# Power.net
KiCad netlist of a schematic drawn in Altium Designer
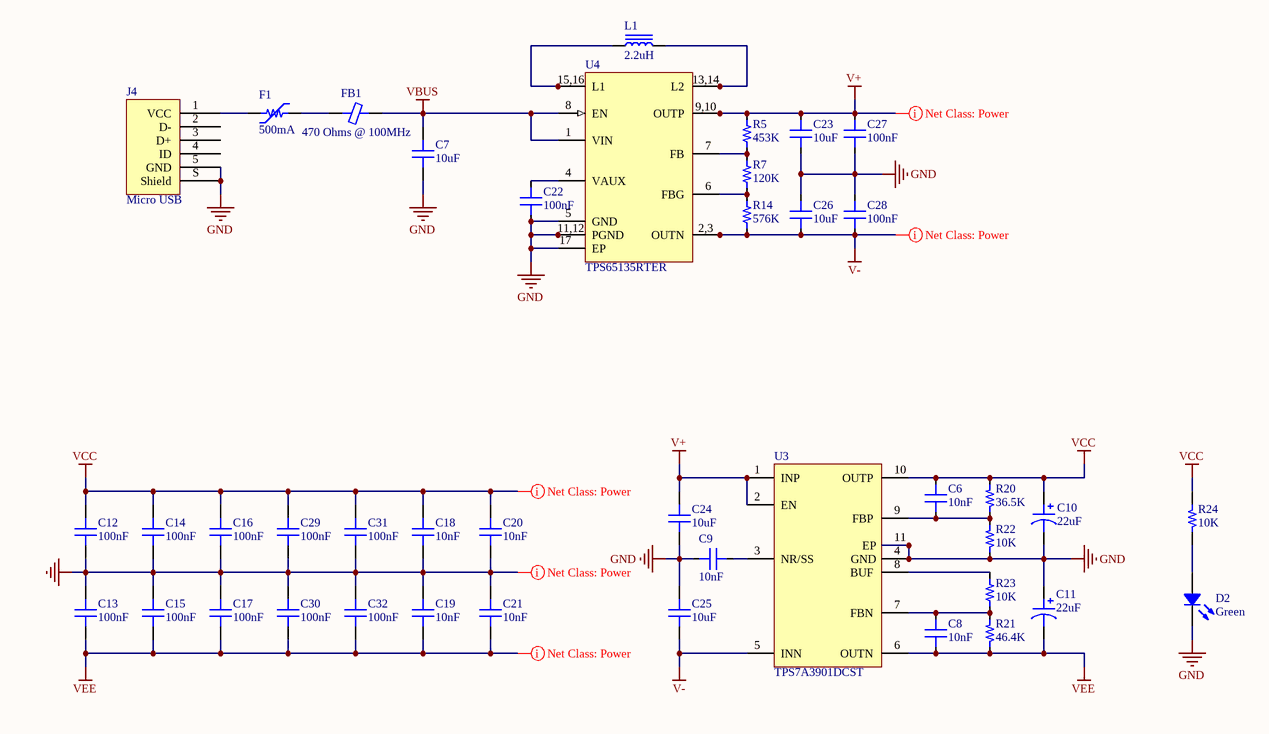
[diagram p0: Power.SchDoc]

(export (version "E")
  (design (tool "Eeschema 10.0.6"))
  (components
    (comp (ref "C6")
      (value "10nF")
      (footprint "CAP 0402/1005")
      (description "CAP CER 10NF 25V NP0 0402")
      (fields (field (name "MANUFACTURER") "Murata") (field (name "TOLERANCE") "2%"))
      (libsource (lib "") (part "Capacitor_1"))
    )
    (comp (ref "C7")
      (value "10uF")
      (footprint "CAP 0603/1608")
      (description "CAP CER 10UF 16V X5R 0603")
      (fields
        (field (name "PART NUMBER") "GRM188R61C106MA73D")
        (field (name "MANUFACTURER") "Murata Electronics North America")
      )
      (libsource (lib "Mengsklib") (part "Capacitor"))
    )
    (comp (ref "C8")
      (value "10nF")
      (footprint "CAP 0402/1005")
      (description "CAP CER 10NF 25V NP0 0402")
      (fields (field (name "MANUFACTURER") "Murata") (field (name "TOLERANCE") "2%"))
      (libsource (lib "") (part "Capacitor_1"))
    )
    (comp (ref "C9")
      (value "10nF")
      (footprint "CAP 0402/1005")
      (description "CAP CER 10NF 25V NP0 0402")
      (fields (field (name "MANUFACTURER") "Murata") (field (name "TOLERANCE") "2%"))
      (libsource (lib "") (part "Capacitor_1"))
    )
    (comp (ref "C10")
      (value "22uF")
      (footprint "CAP TAN 3528 - 2.1MM")
      (description "CAP TANT 22UF 16V 3528")
      (fields (field (name "MANUFACTURER") "AVX") (field (name "TOLERANCE") "20%"))
      (libsource (lib "Mengsklib") (part "Polarised Capacitor"))
    )
    (comp (ref "C11")
      (value "22uF")
      (footprint "CAP TAN 3528 - 2.1MM")
      (description "CAP TANT 22UF 16V 3528")
      (fields (field (name "MANUFACTURER") "AVX") (field (name "TOLERANCE") "20%"))
      (libsource (lib "Mengsklib") (part "Polarised Capacitor"))
    )
    (comp (ref "C12")
      (value "100nF")
      (footprint "CAP 0402/1005")
      (description "CAP CER 100NF 25V X5R 0402")
      (fields (field (name "MANUFACTURER") "Murata") (field (name "TOLERANCE") "10%"))
      (libsource (lib "Mengsklib") (part "Capacitor"))
    )
    (comp (ref "C13")
      (value "100nF")
      (footprint "CAP 0402/1005")
      (description "CAP CER 100NF 25V X5R 0402")
      (fields (field (name "MANUFACTURER") "Murata") (field (name "TOLERANCE") "10%"))
      (libsource (lib "Mengsklib") (part "Capacitor"))
    )
    (comp (ref "C14")
      (value "100nF")
      (footprint "CAP 0204/0510")
      (description "CAP CER 100NF 25V X5R 0204")
      (fields (field (name "PART NUMBER") "MSRLT103SB5104MFNA01") (field (name "MANUFACTURER") "Taiyo Yuden"))
      (libsource (lib "Mengsklib") (part "Capacitor"))
    )
    (comp (ref "C15")
      (value "100nF")
      (footprint "CAP 0204/0510")
      (description "CAP CER 100NF 25V X5R 0204")
      (fields (field (name "PART NUMBER") "MSRLT103SB5104MFNA01") (field (name "MANUFACTURER") "Taiyo Yuden"))
      (libsource (lib "Mengsklib") (part "Capacitor"))
    )
    (comp (ref "C16")
      (value "100nF")
      (footprint "CAP 0204/0510")
      (description "CAP CER 100NF 25V X5R 0204")
      (fields (field (name "PART NUMBER") "MSRLT103SB5104MFNA01") (field (name "MANUFACTURER") "Taiyo Yuden"))
      (libsource (lib "Mengsklib") (part "Capacitor"))
    )
    (comp (ref "C17")
      (value "100nF")
      (footprint "CAP 0204/0510")
      (description "CAP CER 100NF 25V X5R 0204")
      (fields (field (name "PART NUMBER") "MSRLT103SB5104MFNA01") (field (name "MANUFACTURER") "Taiyo Yuden"))
      (libsource (lib "Mengsklib") (part "Capacitor"))
    )
    (comp (ref "C18")
      (value "10nF")
      (footprint "CAP 0402/1005")
      (description "CAP CER 10NF 25V NP0 0402")
      (fields (field (name "PART NUMBER") "GRM1555C1E103GE01D") (field (name "TOLERANCE") "2%"))
      (libsource (lib "Mengsklib") (part "Capacitor"))
    )
    (comp (ref "C19")
      (value "10nF")
      (footprint "CAP 0402/1005")
      (description "CAP CER 10NF 25V NP0 0402")
      (fields (field (name "PART NUMBER") "GRM1555C1E103GE01D") (field (name "TOLERANCE") "2%"))
      (libsource (lib "Mengsklib") (part "Capacitor"))
    )
    (comp (ref "C20")
      (value "10nF")
      (footprint "CAP 0402/1005")
      (description "CAP CER 10NF 25V NP0 0402")
      (fields (field (name "PART NUMBER") "GRM1555C1E103GE01D") (field (name "TOLERANCE") "2%"))
      (libsource (lib "Mengsklib") (part "Capacitor"))
    )
    (comp (ref "C21")
      (value "10nF")
      (footprint "CAP 0402/1005")
      (description "CAP CER 10NF 25V NP0 0402")
      (fields (field (name "PART NUMBER") "GRM1555C1E103GE01D") (field (name "TOLERANCE") "2%"))
      (libsource (lib "Mengsklib") (part "Capacitor"))
    )
    (comp (ref "C22")
      (value "100nF")
      (footprint "CAP 0402/1005")
      (description "CAP CER 100NF 25V X5R 0402")
      (fields (field (name "PART NUMBER") "GRM155R61E104KA87D") (field (name "MANUFACTURER") "Murata"))
      (libsource (lib "") (part "Capacitor_1"))
    )
    (comp (ref "C23")
      (value "10uF")
      (footprint "CAP 0603/1608")
      (description "CAP CER 10UF 16V X5R 0603")
      (fields
        (field (name "PART NUMBER") "GRM188R61C106MA73D")
        (field (name "MANUFACTURER") "Murata Electronics North America")
      )
      (libsource (lib "") (part "Capacitor_1"))
    )
    (comp (ref "C24")
      (value "10uF")
      (footprint "CAP 0603/1608")
      (description "CAP CER 10UF 16V X5R 0603")
      (fields (field (name "MANUFACTURER") "Murata") (field (name "PART NUMBER") "GRM188R61C106MA73D"))
      (libsource (lib "Mengsklib") (part "Capacitor"))
    )
    (comp (ref "C25")
      (value "10uF")
      (footprint "CAP 0603/1608")
      (description "CAP CER 10UF 16V X5R 0603")
      (fields (field (name "MANUFACTURER") "Murata") (field (name "PART NUMBER") "GRM188R61C106MA73D"))
      (libsource (lib "Mengsklib") (part "Capacitor"))
    )
    (comp (ref "C26")
      (value "10uF")
      (footprint "CAP 0603/1608")
      (description "CAP CER 10UF 16V X5R 0603")
      (fields
        (field (name "PART NUMBER") "GRM188R61C106MA73D")
        (field (name "MANUFACTURER") "Murata Electronics North America")
      )
      (libsource (lib "") (part "Capacitor_1"))
    )
    (comp (ref "C27")
      (value "100nF")
      (footprint "CAP 0402/1005")
      (description "CAP CER 100NF 25V X5R 0402")
      (fields
        (field (name "PART NUMBER") "GRM155R61E104KA87D")
        (field (name "MANUFACTURER") "Murata Electronics North America")
      )
      (libsource (lib "") (part "Capacitor_1"))
    )
    (comp (ref "C28")
      (value "100nF")
      (footprint "CAP 0402/1005")
      (description "CAP CER 100NF 25V X5R 0402")
      (fields
        (field (name "PART NUMBER") "GRM155R61E104KA87D")
        (field (name "MANUFACTURER") "Murata Electronics North America")
      )
      (libsource (lib "") (part "Capacitor_1"))
    )
    (comp (ref "C29")
      (value "100nF")
      (footprint "CAP 0204/0510")
      (description "CAP CER 100NF 25V X5R 0204")
      (fields (field (name "MANUFACTURER") "Taiyo Yuden") (field (name "TOLERANCE") "20%"))
      (libsource (lib "Mengsklib") (part "Capacitor"))
    )
    (comp (ref "C30")
      (value "100nF")
      (footprint "CAP 0204/0510")
      (description "CAP CER 100NF 25V X5R 0204")
      (fields (field (name "MANUFACTURER") "Taiyo Yuden") (field (name "TOLERANCE") "20%"))
      (libsource (lib "Mengsklib") (part "Capacitor"))
    )
    (comp (ref "C31")
      (value "100nF")
      (footprint "CAP 0204/0510")
      (description "CAP CER 100NF 25V X5R 0204")
      (fields (field (name "MANUFACTURER") "Taiyo Yuden") (field (name "TOLERANCE") "20%"))
      (libsource (lib "Mengsklib") (part "Capacitor"))
    )
    (comp (ref "C32")
      (value "100nF")
      (footprint "CAP 0204/0510")
      (description "CAP CER 100NF 25V X5R 0204")
      (fields (field (name "MANUFACTURER") "Taiyo Yuden") (field (name "TOLERANCE") "20%"))
      (libsource (lib "Mengsklib") (part "Capacitor"))
    )
    (comp (ref "D2")
      (value "Green")
      (footprint "LED 0805/2012 GREEN")
      (description "LED GREEN CLEAR 0805 SMD")
      (fields (field (name "MANUFACTURER") "Lite-On Inc.") (field (name "PART NUMBER") "LTST-C171KGKT"))
      (libsource (lib "Mengsklib") (part "LED"))
    )
    (comp (ref "F1")
      (value "500mA")
      (footprint "PPTC 1206/3216")
      (description "PTC RESET FUSE 13.2V 500MA 1206")
      (fields (field (name "PART NUMBER") "NANOSMDC050F/13.2-2") (field (name "MANUFACTURER") "Littelfuse"))
      (libsource (lib "Mengsklib") (part "PPTC"))
    )
    (comp (ref "FB1")
      (value "470 Ohms @ 100MHz")
      (footprint "FER 0603/1608")
      (description "FERRITE BEAD 470 OHM 0603 1LN")
      (fields (field (name "PART NUMBER") "MPZ1608B471ATA00") (field (name "MANUFACTURER") "TDK"))
      (libsource (lib "Mengsklib") (part "Ferrite Chip"))
    )
    (comp (ref "J4")
      (value "Micro USB")
      (footprint "FCI USB 10118193-0001LF")
      (description "CONN USB MICRO B RECPT SMT R/A")
      (fields (field (name "PART NUMBER") "10118193-0001LF") (field (name "MANUFACTURER") "FCI"))
      (libsource (lib "Mengsklib") (part "USB 2.0 Type B Micro"))
    )
    (comp (ref "L1")
      (value "2.2uH")
      (footprint "TDK VLS201612CX")
      (description "FIXED IND 2.2UH 1.5A 140 MOHM")
      (fields (field (name "PART NUMBER") "VLS201612CX-2R2M-1") (field (name "MANUFACTURER") "TDK"))
      (libsource (lib "Mengsklib") (part "Inductor"))
    )
    (comp (ref "R5")
      (value "453K")
      (footprint "RES 0402/1005")
      (description "RES SMD 453K OHM 1% 1/16W 0402")
      (fields (field (name "PART NUMBER") "RC0402FR-07453KL") (field (name "MANUFACTURER") "Yageo"))
      (libsource (lib "Mengsklib") (part "Resistor"))
    )
    (comp (ref "R7")
      (value "120K")
      (footprint "RES 0402/1005")
      (description "RES SMD 120K OHM 1% 1/16W 0402")
      (fields (field (name "PART NUMBER") "RC0402FR-07120KL") (field (name "MANUFACTURER") "Yageo"))
      (libsource (lib "Mengsklib") (part "Resistor"))
    )
    (comp (ref "R14")
      (value "576K")
      (footprint "RES 0402/1005")
      (description "RES SMD 576K OHM 1% 1/16W 0402")
      (fields (field (name "PART NUMBER") "RC0402FR-07576KL") (field (name "MANUFACTURER") "Yageo"))
      (libsource (lib "Mengsklib") (part "Resistor"))
    )
    (comp (ref "R20")
      (value "36.5K")
      (footprint "RES 0402/1005")
      (description "RES SMD 36.5K OHM 1% 1/16W 0402")
      (fields (field (name "PART NUMBER") "RC0402FR-0736K5L") (field (name "MANUFACTURER") "Yageo"))
      (libsource (lib "Mengsklib") (part "Resistor"))
    )
    (comp (ref "R21")
      (value "46.4K")
      (footprint "RES 0402/1005")
      (description "RES SMD 46.4K OHM 1% 1/16W 0402")
      (fields (field (name "PART NUMBER") "RC0402FR-0746K4L") (field (name "MANUFACTURER") "Yageo"))
      (libsource (lib "Mengsklib") (part "Resistor"))
    )
    (comp (ref "R22")
      (value "10K")
      (footprint "RES 0402/1005")
      (description "RES SMD 10K OHM 1% 1/16W 0402")
      (fields (field (name "PART NUMBER") "RC0402FR-0710KL") (field (name "MANUFACTURER") "Yageo"))
      (libsource (lib "Mengsklib") (part "Resistor"))
    )
    (comp (ref "R23")
      (value "10K")
      (footprint "RES 0402/1005")
      (description "RES SMD 10K OHM 1% 1/16W 0402")
      (fields (field (name "PART NUMBER") "RC0402FR-0710KL") (field (name "MANUFACTURER") "Yageo"))
      (libsource (lib "Mengsklib") (part "Resistor"))
    )
    (comp (ref "R24")
      (value "10K")
      (footprint "RES 0603/1608")
      (description "RES SMD 10K OHM 5% 1/10W 0603")
      (fields (field (name "PART NUMBER") "RC0603JR-0710KL") (field (name "MANUFACTURER") "Yageo"))
      (libsource (lib "") (part "Resistor_1"))
    )
    (comp (ref "U3")
      (value "TPS7A3901DCST")
      (footprint "DFN50P300X300X80_HS-11N")
      (description "IC REG LIN POS/NEG ADJ 10WSON")
      (fields (field (name "MANUFACTURER") "TI"))
      (libsource (lib "Mengsklib") (part "TPS7A39"))
    )
    (comp (ref "U4")
      (value "TPS65135RTER")
      (footprint "QFN50P305X305X100_HS-17N")
      (description "IC REG BOOST INV DUAL 16WQFN")
      (fields (field (name "MANUFACTURER") "TI"))
      (libsource (lib "Mengsklib") (part "TPS65135"))
    )
  )
  (nets
    (net (code "1") (name "GND") (class "Default")
      (node (ref "C10") (pin "2") (pinfunction "2_2") (pintype "passive"))
      (node (ref "C11") (pin "1") (pinfunction "1_1") (pintype "passive"))
      (node (ref "C12") (pin "2") (pinfunction "2_2") (pintype "passive"))
      (node (ref "C13") (pin "1") (pinfunction "1_1") (pintype "passive"))
      (node (ref "C14") (pin "2") (pinfunction "2_2") (pintype "passive"))
      (node (ref "C15") (pin "1") (pinfunction "1_1") (pintype "passive"))
      (node (ref "C16") (pin "2") (pinfunction "2_2") (pintype "passive"))
      (node (ref "C17") (pin "1") (pinfunction "1_1") (pintype "passive"))
      (node (ref "C18") (pin "2") (pinfunction "2_2") (pintype "passive"))
      (node (ref "C19") (pin "1") (pinfunction "1_1") (pintype "passive"))
      (node (ref "C20") (pin "2") (pinfunction "2_2") (pintype "passive"))
      (node (ref "C21") (pin "1") (pinfunction "1_1") (pintype "passive"))
      (node (ref "C22") (pin "2") (pinfunction "2_2") (pintype "passive"))
      (node (ref "C23") (pin "2") (pinfunction "2_2") (pintype "passive"))
      (node (ref "C24") (pin "2") (pinfunction "2_2") (pintype "passive"))
      (node (ref "C25") (pin "2") (pinfunction "2_2") (pintype "passive"))
      (node (ref "C26") (pin "1") (pinfunction "1_1") (pintype "passive"))
      (node (ref "C27") (pin "2") (pinfunction "2_2") (pintype "passive"))
      (node (ref "C28") (pin "1") (pinfunction "1_1") (pintype "passive"))
      (node (ref "C29") (pin "2") (pinfunction "2_2") (pintype "passive"))
      (node (ref "C30") (pin "1") (pinfunction "1_1") (pintype "passive"))
      (node (ref "C31") (pin "2") (pinfunction "2_2") (pintype "passive"))
      (node (ref "C32") (pin "1") (pinfunction "1_1") (pintype "passive"))
      (node (ref "C7") (pin "1") (pinfunction "1_1") (pintype "passive"))
      (node (ref "C9") (pin "2") (pinfunction "2_2") (pintype "passive"))
      (node (ref "D2") (pin "2") (pinfunction "2_2") (pintype "passive"))
      (node (ref "J4") (pin "5") (pinfunction "GND_5") (pintype "passive"))
      (node (ref "J4") (pin "S") (pinfunction "Shield_S") (pintype "passive"))
      (node (ref "R22") (pin "2") (pinfunction "2_2") (pintype "passive"))
      (node (ref "U3") (pin "11") (pinfunction "EP_11") (pintype "power_in"))
      (node (ref "U3") (pin "4") (pinfunction "GND_4") (pintype "power_in"))
      (node (ref "U4") (pin "11") (pinfunction "PGND_11") (pintype "passive"))
      (node (ref "U4") (pin "12") (pinfunction "PGND_12") (pintype "passive"))
      (node (ref "U4") (pin "17") (pinfunction "EP_17") (pintype "passive"))
      (node (ref "U4") (pin "5") (pinfunction "GND_5") (pintype "passive"))
    )
    (net (code "2") (name "Net-(D2-Pad1)") (class "Default")
      (node (ref "D2") (pin "1") (pinfunction "1_1") (pintype "passive"))
      (node (ref "R24") (pin "2") (pinfunction "2_2") (pintype "passive"))
    )
    (net (code "3") (name "Net-(F1-Pad2)") (class "Default")
      (node (ref "F1") (pin "2") (pinfunction "2_2") (pintype "passive"))
      (node (ref "FB1") (pin "1") (pinfunction "1_1") (pintype "passive"))
    )
    (net (code "4") (name "Net-(J4-VCC)") (class "Default")
      (node (ref "F1") (pin "1") (pinfunction "1_1") (pintype "passive"))
      (node (ref "J4") (pin "1") (pinfunction "VCC_1") (pintype "passive"))
    )
    (net (code "5") (name "Net-(L1-Pad1)") (class "Default")
      (node (ref "L1") (pin "1") (pinfunction "1_1") (pintype "passive"))
      (node (ref "U4") (pin "15") (pinfunction "L1_15") (pintype "passive"))
      (node (ref "U4") (pin "16") (pinfunction "L1_16") (pintype "passive"))
    )
    (net (code "6") (name "Net-(L1-Pad2)") (class "Default")
      (node (ref "L1") (pin "2") (pinfunction "2_2") (pintype "passive"))
      (node (ref "U4") (pin "13") (pinfunction "L2_13") (pintype "passive"))
      (node (ref "U4") (pin "14") (pinfunction "L2_14") (pintype "passive"))
    )
    (net (code "7") (name "Net-(U3-BUF)") (class "Default")
      (node (ref "R23") (pin "2") (pinfunction "2_2") (pintype "passive"))
      (node (ref "U3") (pin "8") (pinfunction "BUF_8") (pintype "power_in"))
    )
    (net (code "8") (name "Net-(U3-FBN)") (class "Default")
      (node (ref "C8") (pin "1") (pinfunction "1_1") (pintype "passive"))
      (node (ref "R21") (pin "1") (pinfunction "1_1") (pintype "passive"))
      (node (ref "R23") (pin "1") (pinfunction "1_1") (pintype "passive"))
      (node (ref "U3") (pin "7") (pinfunction "FBN_7") (pintype "power_in"))
    )
    (net (code "9") (name "Net-(U3-FBP)") (class "Default")
      (node (ref "C6") (pin "1") (pinfunction "1_1") (pintype "passive"))
      (node (ref "R20") (pin "2") (pinfunction "2_2") (pintype "passive"))
      (node (ref "R22") (pin "1") (pinfunction "1_1") (pintype "passive"))
      (node (ref "U3") (pin "9") (pinfunction "FBP_9") (pintype "power_in"))
    )
    (net (code "10") (name "Net-(U3-NR{slash}SS)") (class "Default")
      (node (ref "C9") (pin "1") (pinfunction "1_1") (pintype "passive"))
      (node (ref "U3") (pin "3") (pinfunction "NR/SS_3") (pintype "power_in"))
    )
    (net (code "11") (name "Net-(U4-FB)") (class "Default")
      (node (ref "R5") (pin "1") (pinfunction "1_1") (pintype "passive"))
      (node (ref "R7") (pin "2") (pinfunction "2_2") (pintype "passive"))
      (node (ref "U4") (pin "7") (pinfunction "FB_7") (pintype "passive"))
    )
    (net (code "12") (name "Net-(U4-FBG)") (class "Default")
      (node (ref "R14") (pin "2") (pinfunction "2_2") (pintype "passive"))
      (node (ref "R7") (pin "1") (pinfunction "1_1") (pintype "passive"))
      (node (ref "U4") (pin "6") (pinfunction "FBG_6") (pintype "passive"))
    )
    (net (code "13") (name "Net-(U4-VAUX)") (class "Default")
      (node (ref "C22") (pin "1") (pinfunction "1_1") (pintype "passive"))
      (node (ref "U4") (pin "4") (pinfunction "VAUX_4") (pintype "passive"))
    )
    (net (code "14") (name "V+") (class "Default")
      (node (ref "C23") (pin "1") (pinfunction "1_1") (pintype "passive"))
      (node (ref "C24") (pin "1") (pinfunction "1_1") (pintype "passive"))
      (node (ref "C27") (pin "1") (pinfunction "1_1") (pintype "passive"))
      (node (ref "R5") (pin "2") (pinfunction "2_2") (pintype "passive"))
      (node (ref "U3") (pin "1") (pinfunction "INP_1") (pintype "power_in"))
      (node (ref "U3") (pin "2") (pinfunction "EN_2") (pintype "power_in"))
      (node (ref "U4") (pin "10") (pinfunction "OUTP_10") (pintype "power_in"))
      (node (ref "U4") (pin "9") (pinfunction "OUTP_9") (pintype "passive"))
    )
    (net (code "15") (name "V-") (class "Default")
      (node (ref "C25") (pin "1") (pinfunction "1_1") (pintype "passive"))
      (node (ref "C26") (pin "2") (pinfunction "2_2") (pintype "passive"))
      (node (ref "C28") (pin "2") (pinfunction "2_2") (pintype "passive"))
      (node (ref "R14") (pin "1") (pinfunction "1_1") (pintype "passive"))
      (node (ref "U3") (pin "5") (pinfunction "INN_5") (pintype "power_in"))
      (node (ref "U4") (pin "2") (pinfunction "OUTN_2") (pintype "power_in"))
      (node (ref "U4") (pin "3") (pinfunction "OUTN_3") (pintype "power_in"))
    )
    (net (code "16") (name "VBUS") (class "Default")
      (node (ref "C7") (pin "2") (pinfunction "2_2") (pintype "passive"))
      (node (ref "FB1") (pin "2") (pinfunction "2_2") (pintype "passive"))
      (node (ref "U4") (pin "1") (pinfunction "VIN_1") (pintype "power_in"))
      (node (ref "U4") (pin "8") (pinfunction "EN_8") (pintype "input"))
    )
    (net (code "17") (name "VCC") (class "Default")
      (node (ref "C10") (pin "1") (pinfunction "1_1") (pintype "passive"))
      (node (ref "C12") (pin "1") (pinfunction "1_1") (pintype "passive"))
      (node (ref "C14") (pin "1") (pinfunction "1_1") (pintype "passive"))
      (node (ref "C16") (pin "1") (pinfunction "1_1") (pintype "passive"))
      (node (ref "C18") (pin "1") (pinfunction "1_1") (pintype "passive"))
      (node (ref "C20") (pin "1") (pinfunction "1_1") (pintype "passive"))
      (node (ref "C29") (pin "1") (pinfunction "1_1") (pintype "passive"))
      (node (ref "C31") (pin "1") (pinfunction "1_1") (pintype "passive"))
      (node (ref "C6") (pin "2") (pinfunction "2_2") (pintype "passive"))
      (node (ref "R20") (pin "1") (pinfunction "1_1") (pintype "passive"))
      (node (ref "R24") (pin "1") (pinfunction "1_1") (pintype "passive"))
      (node (ref "U3") (pin "10") (pinfunction "OUTP_10") (pintype "power_in"))
    )
    (net (code "18") (name "VEE") (class "Default")
      (node (ref "C11") (pin "2") (pinfunction "2_2") (pintype "passive"))
      (node (ref "C13") (pin "2") (pinfunction "2_2") (pintype "passive"))
      (node (ref "C15") (pin "2") (pinfunction "2_2") (pintype "passive"))
      (node (ref "C17") (pin "2") (pinfunction "2_2") (pintype "passive"))
      (node (ref "C19") (pin "2") (pinfunction "2_2") (pintype "passive"))
      (node (ref "C21") (pin "2") (pinfunction "2_2") (pintype "passive"))
      (node (ref "C30") (pin "2") (pinfunction "2_2") (pintype "passive"))
      (node (ref "C32") (pin "2") (pinfunction "2_2") (pintype "passive"))
      (node (ref "C8") (pin "2") (pinfunction "2_2") (pintype "passive"))
      (node (ref "R21") (pin "2") (pinfunction "2_2") (pintype "passive"))
      (node (ref "U3") (pin "6") (pinfunction "OUTN_6") (pintype "power_in"))
    )
    (net (code "19") (name "unconnected-(J4-D+-Pad3)") (class "Default")
      (node (ref "J4") (pin "3") (pinfunction "D+_3") (pintype "passive"))
    )
    (net (code "20") (name "unconnected-(J4-D--Pad2)") (class "Default")
      (node (ref "J4") (pin "2") (pinfunction "D-_2") (pintype "passive"))
    )
    (net (code "21") (name "unconnected-(J4-ID-Pad4)") (class "Default")
      (node (ref "J4") (pin "4") (pinfunction "ID_4") (pintype "passive"))
    )
  )
)
